# Sheet1.net
KiCad netlist of a schematic drawn in Altium Designer
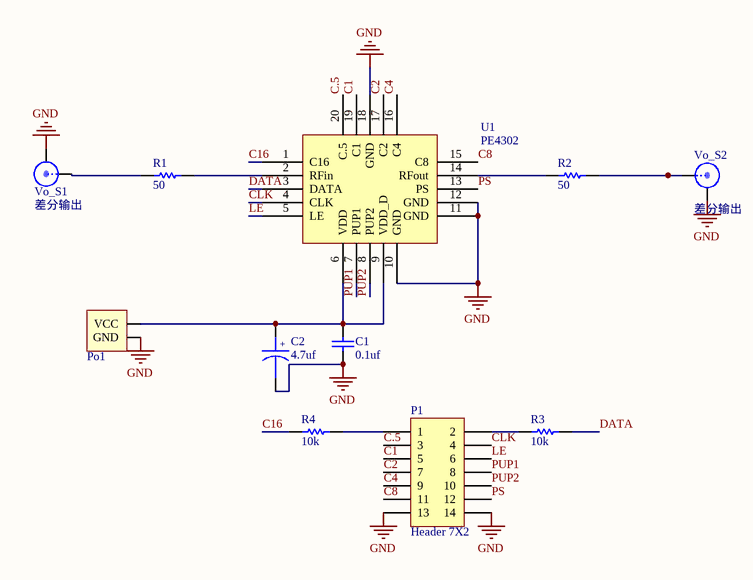
[diagram p0: Sheet1.SchDoc]

(export (version "E")
  (design (tool "Eeschema 10.0.6"))
  (components
    (comp (ref "C1") (value "0.1uf") (footprint "0603C") (libsource (lib "Schlib1") (part "Cap")))
    (comp (ref "C2")
      (value "4.7uf")
      (footprint "7343-31 TYPE D")
      (libsource (lib "Schlib1") (part "Tantalium Cap"))
    )
    (comp (ref "P1")
      (value "Header 7X2")
      (footprint "HDR2X7")
      (description "Header, 7-Pin, Dual row")
      (fields (field (name "PUBLISHER") "Altium Limited"))
      (libsource (lib "Miscellaneous Connectors") (part "Header 7X2"))
    )
    (comp (ref "Po1")
      (value "Power_2Port")
      (footprint "Power_S_2Port")
      (libsource (lib "Schlib1") (part "Power_2Port"))
    )
    (comp (ref "R1") (value "50") (footprint "0805") (libsource (lib "Schlib1") (part "Res")))
    (comp (ref "R2") (value "50") (footprint "0805") (libsource (lib "Schlib1") (part "Res")))
    (comp (ref "R3") (value "10k") (footprint "0603R") (libsource (lib "Schlib1") (part "Res")))
    (comp (ref "R4") (value "10k") (footprint "0603R") (libsource (lib "Schlib1") (part "Res")))
    (comp (ref "U1")
      (value "PE4302")
      (footprint "LC-QFN-20_4x4x05P")
      (libsource (lib "Schlib1") (part "PE4302"))
    )
    (comp (ref "Vo_S1") (value "差分输出") (footprint "SMA-LYING") (libsource (lib "Schlib1") (part "SMA")))
    (comp (ref "Vo_S2") (value "差分输出") (footprint "SMA-LYING") (libsource (lib "Schlib1") (part "SMA")))
  )
  (nets
    (net (code "1") (name "/C.5") (class "Default")
      (node (ref "P1") (pin "3") (pinfunction "3_3") (pintype "passive"))
      (node (ref "U1") (pin "20") (pinfunction "C.5_20") (pintype "passive"))
    )
    (net (code "2") (name "/C1") (class "Default")
      (node (ref "P1") (pin "5") (pinfunction "5_5") (pintype "passive"))
      (node (ref "U1") (pin "19") (pinfunction "C1_19") (pintype "passive"))
    )
    (net (code "3") (name "/C2") (class "Default")
      (node (ref "P1") (pin "7") (pinfunction "7_7") (pintype "passive"))
      (node (ref "U1") (pin "17") (pinfunction "C2_17") (pintype "passive"))
    )
    (net (code "4") (name "/C4") (class "Default")
      (node (ref "P1") (pin "9") (pinfunction "9_9") (pintype "passive"))
      (node (ref "U1") (pin "16") (pinfunction "C4_16") (pintype "passive"))
    )
    (net (code "5") (name "/C8") (class "Default")
      (node (ref "P1") (pin "11") (pinfunction "11_11") (pintype "passive"))
      (node (ref "U1") (pin "15") (pinfunction "C8_15") (pintype "passive"))
    )
    (net (code "6") (name "/C16") (class "Default")
      (node (ref "R4") (pin "1") (pinfunction "1_1") (pintype "passive"))
      (node (ref "U1") (pin "1") (pinfunction "C16_1") (pintype "passive"))
    )
    (net (code "7") (name "/CLK") (class "Default")
      (node (ref "P1") (pin "4") (pinfunction "4_4") (pintype "passive"))
      (node (ref "U1") (pin "4") (pinfunction "CLK_4") (pintype "passive"))
    )
    (net (code "8") (name "/DATA") (class "Default")
      (node (ref "R3") (pin "2") (pinfunction "2_2") (pintype "passive"))
      (node (ref "U1") (pin "3") (pinfunction "DATA_3") (pintype "passive"))
    )
    (net (code "9") (name "/LE") (class "Default")
      (node (ref "P1") (pin "6") (pinfunction "6_6") (pintype "passive"))
      (node (ref "U1") (pin "5") (pinfunction "LE_5") (pintype "passive"))
    )
    (net (code "10") (name "/PS") (class "Default")
      (node (ref "P1") (pin "12") (pinfunction "12_12") (pintype "passive"))
      (node (ref "U1") (pin "13") (pinfunction "PS_13") (pintype "passive"))
    )
    (net (code "11") (name "/PUP1") (class "Default")
      (node (ref "P1") (pin "8") (pinfunction "8_8") (pintype "passive"))
      (node (ref "U1") (pin "7") (pinfunction "PUP1_7") (pintype "passive"))
    )
    (net (code "12") (name "/PUP2") (class "Default")
      (node (ref "P1") (pin "10") (pinfunction "10_10") (pintype "passive"))
      (node (ref "U1") (pin "8") (pinfunction "PUP2_8") (pintype "passive"))
    )
    (net (code "13") (name "GND") (class "Default")
      (node (ref "C1") (pin "1") (pinfunction "1_1") (pintype "passive"))
      (node (ref "C2") (pin "2") (pinfunction "2_2") (pintype "passive"))
      (node (ref "P1") (pin "13") (pinfunction "13_13") (pintype "passive"))
      (node (ref "P1") (pin "14") (pinfunction "14_14") (pintype "passive"))
      (node (ref "Po1") (pin "2") (pinfunction "GND_2") (pintype "passive"))
      (node (ref "U1") (pin "10") (pinfunction "GND_10") (pintype "passive"))
      (node (ref "U1") (pin "11") (pinfunction "GND_11") (pintype "passive"))
      (node (ref "U1") (pin "12") (pinfunction "GND_12") (pintype "passive"))
      (node (ref "U1") (pin "18") (pinfunction "GND_18") (pintype "passive"))
      (node (ref "Vo_S1") (pin "1") (pinfunction "1_1") (pintype "passive"))
      (node (ref "Vo_S2") (pin "1") (pinfunction "1_1") (pintype "passive"))
    )
    (net (code "14") (name "Net-(P1-Pad1)") (class "Default")
      (node (ref "P1") (pin "1") (pinfunction "1_1") (pintype "passive"))
      (node (ref "R4") (pin "2") (pinfunction "2_2") (pintype "passive"))
    )
    (net (code "15") (name "Net-(P1-Pad2)") (class "Default")
      (node (ref "P1") (pin "2") (pinfunction "2_2") (pintype "passive"))
      (node (ref "R3") (pin "1") (pinfunction "1_1") (pintype "passive"))
    )
    (net (code "16") (name "Net-(Po1-VCC)") (class "Default")
      (node (ref "C1") (pin "2") (pinfunction "2_2") (pintype "passive"))
      (node (ref "C2") (pin "1") (pinfunction "1_1") (pintype "passive"))
      (node (ref "Po1") (pin "1") (pinfunction "VCC_1") (pintype "passive"))
      (node (ref "U1") (pin "6") (pinfunction "VDD_6") (pintype "passive"))
      (node (ref "U1") (pin "9") (pinfunction "VDD_D_9") (pintype "passive"))
    )
    (net (code "17") (name "Net-(R1-Pad1)") (class "Default")
      (node (ref "R1") (pin "1") (pinfunction "1_1") (pintype "passive"))
      (node (ref "Vo_S1") (pin "0") (pinfunction "0_0") (pintype "passive"))
    )
    (net (code "18") (name "Net-(R2-Pad2)") (class "Default")
      (node (ref "R2") (pin "2") (pinfunction "2_2") (pintype "passive"))
      (node (ref "Vo_S2") (pin "0") (pinfunction "0_0") (pintype "passive"))
    )
    (net (code "19") (name "Net-(U1-RFin)") (class "Default")
      (node (ref "R1") (pin "2") (pinfunction "2_2") (pintype "passive"))
      (node (ref "U1") (pin "2") (pinfunction "RFin_2") (pintype "passive"))
    )
    (net (code "20") (name "Net-(U1-RFout)") (class "Default")
      (node (ref "R2") (pin "1") (pinfunction "1_1") (pintype "passive"))
      (node (ref "U1") (pin "14") (pinfunction "RFout_14") (pintype "passive"))
    )
  )
)
